# boost_regulator_MIC2288.net
KiCad netlist of a schematic drawn in EAGLE
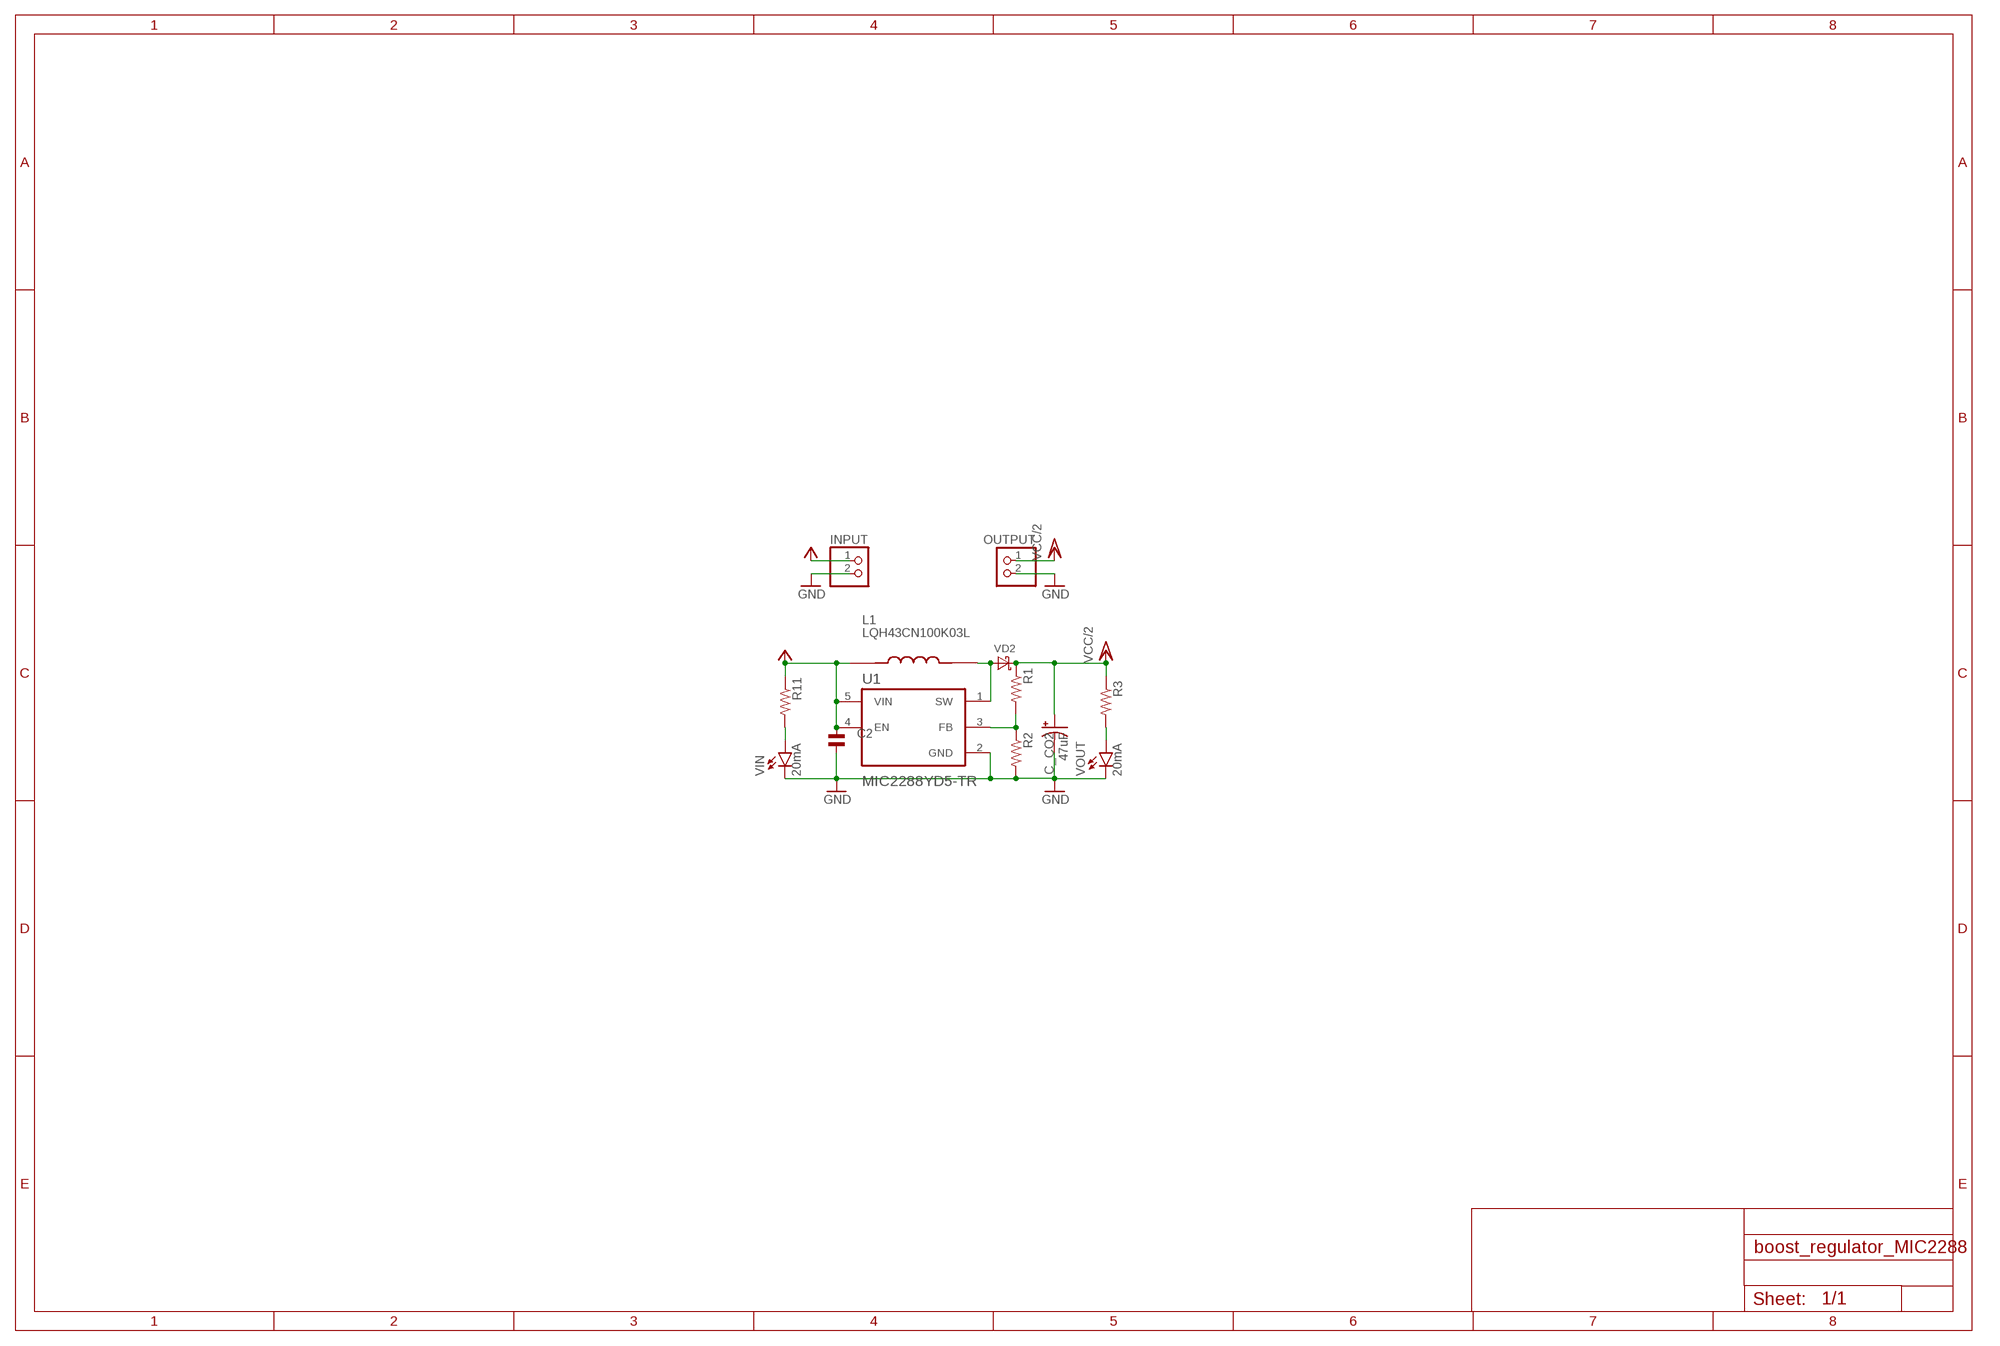
[diagram p0: schematic, sheet 1]

(export (version "E")
  (design (tool "Eeschema 10.0.6"))
  (components
    (comp (ref "C2")
      (value "10uF")
      (footprint "eagle-import:RC-MASTER-SMD_C0603MP")
      (libsource (lib "eagle-import") (part "RC-MASTER-SMD_C_0603MP"))
    )
    (comp (ref "C_CO2")
      (value "47uF")
      (footprint "eagle-import:PANASONIC_C")
      (libsource (lib "eagle-import") (part "22UF-POLAR-PANASONIC_C-35V-20%"))
    )
    (comp (ref "INPUT")
      (value "PINHD-1X2")
      (footprint "eagle-import:1X02")
      (libsource (lib "eagle-import") (part "PINHD-1X2"))
    )
    (comp (ref "L1")
      (value "LQH43CN100K03L")
      (footprint "eagle-import:IND_LQH43CN100K03L")
      (fields (field (name "MF") "Murata"))
      (libsource (lib "eagle-import") (part "LQH43CN100K03L"))
    )
    (comp (ref "OUTPUT")
      (value "PINHD-1X2")
      (footprint "eagle-import:1X02")
      (libsource (lib "eagle-import") (part "PINHD-1X2"))
    )
    (comp (ref "R1")
      (value "47K")
      (footprint "eagle-import:RC-MASTER-SMD_R0603MP")
      (libsource (lib "eagle-import") (part "RC-MASTER-SMD_R_0603MP"))
    )
    (comp (ref "R2")
      (value "5K1")
      (footprint "eagle-import:RC-MASTER-SMD_R0603MP")
      (libsource (lib "eagle-import") (part "RC-MASTER-SMD_R_0603MP"))
    )
    (comp (ref "R3")
      (value "1K")
      (footprint "eagle-import:RC-MASTER-SMD_R0603MP")
      (libsource (lib "eagle-import") (part "RC-MASTER-SMD_R_0603MP"))
    )
    (comp (ref "R11")
      (value "100R")
      (footprint "eagle-import:RC-MASTER-SMD_R0603MP")
      (libsource (lib "eagle-import") (part "RC-MASTER-SMD_R_0603MP"))
    )
    (comp (ref "U1")
      (value "MIC2288YD5-TR")
      (footprint "eagle-import:SOT95P280X100-5N")
      (fields (field (name "MF") "Microchip Technology"))
      (libsource (lib "eagle-import") (part "MIC2288YD5-TR"))
    )
    (comp (ref "VD2")
      (value "DIODE-SCHOTTKY-SOD123")
      (footprint "eagle-import:SOD123")
      (libsource (lib "eagle-import") (part "DIODE-SCHOTTKY-SOD123"))
    )
    (comp (ref "VIN")
      (value "20mA")
      (footprint "eagle-import:CHIP-LED0603")
      (libsource (lib "eagle-import") (part "LEDCHIP-LED0603"))
    )
    (comp (ref "VOUT")
      (value "20mA")
      (footprint "eagle-import:CHIP-LED0603")
      (libsource (lib "eagle-import") (part "LEDCHIP-LED0603"))
    )
  )
  (nets
    (net (code "1") (name "GND") (class "Default")
      (node (ref "C2") (pin "2") (pinfunction "2_2") (pintype "passive"))
      (node (ref "C_CO2") (pin "-") (pinfunction "-_-") (pintype "passive"))
      (node (ref "INPUT") (pin "2") (pinfunction "2_2") (pintype "passive"))
      (node (ref "OUTPUT") (pin "2") (pinfunction "2_2") (pintype "passive"))
      (node (ref "R2") (pin "2") (pinfunction "2_2") (pintype "passive"))
      (node (ref "U1") (pin "2") (pinfunction "GND_2") (pintype "power_in"))
      (node (ref "VIN") (pin "C") (pinfunction "C_C") (pintype "passive"))
      (node (ref "VOUT") (pin "C") (pinfunction "C_C") (pintype "passive"))
    )
    (net (code "2") (name "Net-(R3-Pad2)") (class "Default")
      (node (ref "R3") (pin "2") (pinfunction "2_2") (pintype "passive"))
      (node (ref "VOUT") (pin "A") (pinfunction "A_A") (pintype "passive"))
    )
    (net (code "3") (name "Net-(R11-Pad2)") (class "Default")
      (node (ref "R11") (pin "2") (pinfunction "2_2") (pintype "passive"))
      (node (ref "VIN") (pin "A") (pinfunction "A_A") (pintype "passive"))
    )
    (net (code "4") (name "Net-(U1-FB)") (class "Default")
      (node (ref "R1") (pin "2") (pinfunction "2_2") (pintype "passive"))
      (node (ref "R2") (pin "1") (pinfunction "1_1") (pintype "passive"))
      (node (ref "U1") (pin "3") (pinfunction "FB_3") (pintype "input"))
    )
    (net (code "5") (name "Net-(U1-SW)") (class "Default")
      (node (ref "L1") (pin "2") (pinfunction "2_2") (pintype "passive"))
      (node (ref "U1") (pin "1") (pinfunction "SW_1") (pintype "input"))
      (node (ref "VD2") (pin "A") (pinfunction "A_A") (pintype "passive"))
    )
    (net (code "6") (name "VCC") (class "Default")
      (node (ref "C2") (pin "1") (pinfunction "1_1") (pintype "passive"))
      (node (ref "INPUT") (pin "1") (pinfunction "1_1") (pintype "passive"))
      (node (ref "L1") (pin "1") (pinfunction "1_1") (pintype "passive"))
      (node (ref "R11") (pin "1") (pinfunction "1_1") (pintype "passive"))
      (node (ref "U1") (pin "4") (pinfunction "EN_4") (pintype "input"))
      (node (ref "U1") (pin "5") (pinfunction "VIN_5") (pintype "input"))
    )
    (net (code "7") (name "VCC{slash}2") (class "Default")
      (node (ref "C_CO2") (pin "+") (pinfunction "+_+") (pintype "passive"))
      (node (ref "OUTPUT") (pin "1") (pinfunction "1_1") (pintype "passive"))
      (node (ref "R1") (pin "1") (pinfunction "1_1") (pintype "passive"))
      (node (ref "R3") (pin "1") (pinfunction "1_1") (pintype "passive"))
      (node (ref "VD2") (pin "C") (pinfunction "C_C") (pintype "passive"))
    )
  )
)
